# Sheet1.net
KiCad netlist of a schematic drawn in Altium Designer
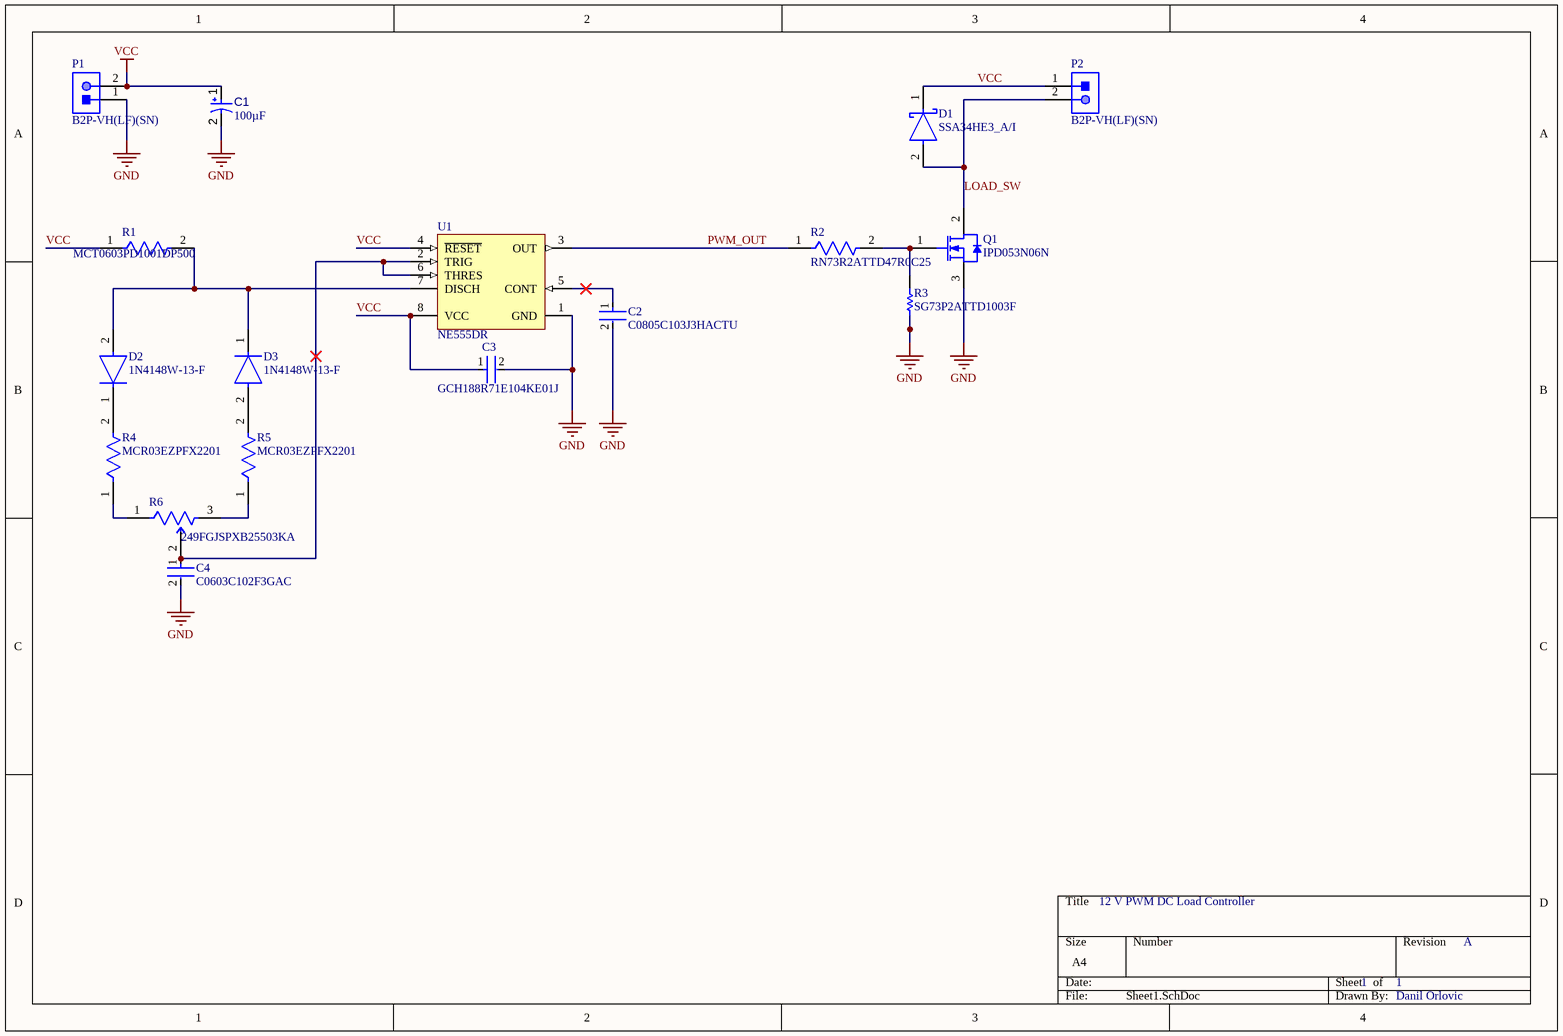
[diagram p0: Sheet1.SchDoc]

(export (version "E")
  (design (tool "Eeschema 10.0.6"))
  (components
    (comp (ref "C1")
      (value "100µF")
      (footprint "CAPPR65-350-1150X800X1250")
      (description "Aluminum Electrolytic Capacitor, 100 uF, +/- 20%, 50 V, -40 to 85 degC, 2-Pin THD, RoHS, Bulk")
      (fields (field (name "MANUFACTURER") "Panasonic") (field (name "TOLERANCE") "20%"))
      (libsource (lib "Danil Orlovic") (part "CAP-P-2"))
    )
    (comp (ref "C2")
      (value "C0805C103J3HACTU")
      (footprint "FP-C0805C-DN-MFG")
      (description "CAP CER 10000PF 25V X8R 0805")
      (fields (field (name "TOLERANCE") "0.05") (field (name "MANUFACTURER") "KEMET"))
      (libsource (lib "Altium Content Vault") (part "b4654b650e69147ec39a6b967a45e02"))
    )
    (comp (ref "C3")
      (value "GCH188R71E104KE01J")
      (footprint "FP-GCH188-0_1-e0_2_0_5-IPC_A")
      (description "Ceramic Capacitor 100nF ±10% 25V X7R 0603")
      (libsource (lib "Altium Content Vault") (part "b4654b650e69147ec39a6b967a45e02"))
    )
    (comp (ref "C4")
      (value "C0603C102F3GAC")
      (footprint "FP-C0603C-CF-MFG")
      (description "C0603 1,000 pF C0G 30ppm/°C 1.00% 25 V")
      (fields
        (field (name "OCTOPART") "https://octopart.com/c0603c102f3gac-kemet-9143535")
        (field (name "TOLERANCE") "0.01")
      )
      (libsource (lib "Altium Content Vault") (part "b4654b650e69147ec39a6b967a45e02"))
    )
    (comp (ref "D1")
      (value "SSA34HE3_A/I")
      (footprint "FP-95400-MFG")
      (description "DIODE SCHOTTKY 40V 3A DO214AC")
      (libsource (lib "Altium Content Vault") (part "1d6ec82d83fb6aee721767c19dac4b9"))
    )
    (comp (ref "D2")
      (value "1N4148W-13-F")
      (footprint "FP-SOD123-MFG")
      (description "DIODE GEN PURP 100V 150MA SOD123")
      (fields
        (field (name "OCTOPART") "https://octopart.com/1n4148w-13-f-diodes+inc.-2359612")
        (field (name "MANUFACTURER") "Diodes Inc.")
      )
      (libsource (lib "Altium Content Vault") (part "d7152d700b627762746794eb795d46e"))
    )
    (comp (ref "D3")
      (value "1N4148W-13-F")
      (footprint "FP-SOD123-MFG")
      (description "DIODE GEN PURP 100V 150MA SOD123")
      (fields
        (field (name "OCTOPART") "https://octopart.com/1n4148w-13-f-diodes+inc.-2359612")
        (field (name "MANUFACTURER") "Diodes Inc.")
      )
      (libsource (lib "Altium Content Vault") (part "d7152d700b627762746794eb795d46e"))
    )
    (comp (ref "P1")
      (value "B2P-VH(LF)(SN)")
      (footprint "JST-B2P-VH(LF)(SN)_V")
      (fields (field (name "MANUFACTURER") "JST"))
      (libsource (lib "Danil Orlovic") (part "CN-1P-M-R2"))
    )
    (comp (ref "P2")
      (value "B2P-VH(LF)(SN)")
      (footprint "JST-B2P-VH(LF)(SN)_V")
      (fields (field (name "MANUFACTURER") "JST"))
      (libsource (lib "") (part "CN-1P-M-R2_1"))
    )
    (comp (ref "Q1")
      (value "IPD053N06N")
      (footprint "INF-PG-TO252-3-11_A_M")
      (description "N-Channel OptiMOS Power-Transistor, 60 V VDS, 45 A ID, -55 to 175 degC, PG-TO252-3-11, Reel, Green")
      (fields (field (name "MANUFACTURER") "Infineon"))
      (libsource (lib "Altium Content Vault") (part "INF-NEMOS-GDS-3"))
    )
    (comp (ref "R1")
      (value "MCT0603PD1001DP500")
      (footprint "FP-MCT0603-IPC_C")
      (description "RES SMD 100 OHM 1% 1/8W 0603")
      (fields (field (name "TOLERANCE") "0.5%"))
      (libsource (lib "Altium Content Vault") (part "1029c3af85768c4190bb7ad29bc67b5"))
    )
    (comp (ref "R2")
      (value "RN73R2ATTD47R0C25")
      (footprint "FP-RN73R2A-IPC_B")
      (description "47Ω ±0.25% 0.125W, 1/8W Chip Resistor 0805 (2012 Metric) Moisture Resistant Thin Film")
      (libsource (lib "Altium Content Vault") (part "1029c3af85768c4190bb7ad29bc67b5"))
    )
    (comp (ref "R3")
      (value "SG73P2ATTD1003F")
      (footprint "RESC2013X60X30NL20T20")
      (fields (field (name "MANUFACTURER") "KOA Speer"))
      (libsource (lib "Altium Content Vault") (part "RES"))
    )
    (comp (ref "R4")
      (value "MCR03EZPFX2201")
      (footprint "FP-MCR03-IPC_C")
      (description "Thick Film Chip Resistor, 0603, 2.2kΩ, 1%, 100ppm/°C, 0.1W, 50V")
      (fields (field (name "TOLERANCE") "1%"))
      (libsource (lib "Altium Content Vault") (part "1029c3af85768c4190bb7ad29bc67b5"))
    )
    (comp (ref "R5")
      (value "MCR03EZPFX2201")
      (footprint "FP-MCR03-IPC_C")
      (description "Thick Film Chip Resistor, 0603, 2.2kΩ, 1%, 100ppm/°C, 0.1W, 50V")
      (fields (field (name "TOLERANCE") "1%"))
      (libsource (lib "Altium Content Vault") (part "1029c3af85768c4190bb7ad29bc67b5"))
    )
    (comp (ref "R6")
      (value "249FGJSPXB25503KA")
      (footprint "FP-249FGJSPXB25503KA-MFG")
      (fields (field (name "TOLERANCE") "10%"))
      (libsource (lib "Altium Content Vault") (part "a77ee20e32664c43a3a1dd5392b6021"))
    )
    (comp (ref "U1")
      (value "NE555DR")
      (footprint "D0008A_N")
      (description "Precision Timer, 4.5 to 16 V, 0 to 70 degC, 8-Pin SOIC (D), Green (RoHS & no Sb/Br), Tape and Reel")
      (fields (field (name "MANUFACTURER") "Texas Instruments"))
      (libsource (lib "Danil Orlovic") (part "TI-NE555-P-8"))
    )
  )
  (nets
    (net (code "2") (name "/LOAD_SW") (class "Default")
      (node (ref "D1") (pin "2") (pinfunction "A_2") (pintype "passive"))
      (node (ref "P2") (pin "2") (pinfunction "2_2") (pintype "passive"))
      (node (ref "Q1") (pin "2") (pinfunction "DRAIN_2") (pintype "passive"))
    )
    (net (code "3") (name "/PWM_OUT") (class "Default")
      (node (ref "R2") (pin "1") (pinfunction "1_1") (pintype "passive"))
      (node (ref "U1") (pin "3") (pinfunction "OUT_3") (pintype "output"))
    )
    (net (code "4") (name "GND") (class "Default")
      (node (ref "C1") (pin "2") (pinfunction "2_2") (pintype "passive"))
      (node (ref "C2") (pin "2") (pinfunction "2_2") (pintype "passive"))
      (node (ref "C3") (pin "2") (pinfunction "2_2") (pintype "passive"))
      (node (ref "C4") (pin "2") (pinfunction "2_2") (pintype "passive"))
      (node (ref "P1") (pin "1") (pinfunction "1_1") (pintype "passive"))
      (node (ref "Q1") (pin "3") (pinfunction "SOURCE_3") (pintype "passive"))
      (node (ref "R3") (pin "1") (pinfunction "1_1") (pintype "passive"))
      (node (ref "U1") (pin "1") (pinfunction "GND_1") (pintype "power_in"))
    )
    (net (code "5") (name "Net-(D2-A)") (class "Default")
      (node (ref "D2") (pin "2") (pinfunction "A_2") (pintype "passive"))
      (node (ref "D3") (pin "1") (pinfunction "C_1") (pintype "passive"))
      (node (ref "R1") (pin "2") (pinfunction "2_2") (pintype "passive"))
      (node (ref "U1") (pin "7") (pinfunction "DISCH_7") (pintype "open_collector"))
    )
    (net (code "6") (name "Net-(D2-C)") (class "Default")
      (node (ref "D2") (pin "1") (pinfunction "C_1") (pintype "passive"))
      (node (ref "R4") (pin "2") (pinfunction "2_2") (pintype "passive"))
    )
    (net (code "7") (name "Net-(D3-A)") (class "Default")
      (node (ref "D3") (pin "2") (pinfunction "A_2") (pintype "passive"))
      (node (ref "R5") (pin "2") (pinfunction "2_2") (pintype "passive"))
    )
    (net (code "8") (name "Net-(Q1-GATE)") (class "Default")
      (node (ref "Q1") (pin "1") (pinfunction "GATE_1") (pintype "passive"))
      (node (ref "R2") (pin "2") (pinfunction "2_2") (pintype "passive"))
      (node (ref "R3") (pin "2") (pinfunction "2_2") (pintype "passive"))
    )
    (net (code "9") (name "Net-(R4-Pad1)") (class "Default")
      (node (ref "R4") (pin "1") (pinfunction "1_1") (pintype "passive"))
      (node (ref "R6") (pin "1") (pinfunction "1_1") (pintype "passive"))
    )
    (net (code "10") (name "Net-(R5-Pad1)") (class "Default")
      (node (ref "R5") (pin "1") (pinfunction "1_1") (pintype "passive"))
      (node (ref "R6") (pin "3") (pinfunction "3_3") (pintype "passive"))
    )
    (net (code "11") (name "Net-(U1-CONT)") (class "Default")
      (node (ref "C2") (pin "1") (pinfunction "1_1") (pintype "passive"))
      (node (ref "U1") (pin "5") (pinfunction "CONT_5") (pintype "input"))
    )
    (net (code "12") (name "Net-(U1-THRES)") (class "Default")
      (node (ref "C4") (pin "1") (pinfunction "1_1") (pintype "passive"))
      (node (ref "R6") (pin "2") (pinfunction "2_2") (pintype "passive"))
      (node (ref "U1") (pin "2") (pinfunction "TRIG_2") (pintype "input"))
      (node (ref "U1") (pin "6") (pinfunction "THRES_6") (pintype "input"))
    )
    (net (code "13") (name "VCC") (class "Default")
      (node (ref "C1") (pin "1") (pinfunction "1_1") (pintype "passive"))
      (node (ref "C3") (pin "1") (pinfunction "1_1") (pintype "passive"))
      (node (ref "D1") (pin "1") (pinfunction "C_1") (pintype "passive"))
      (node (ref "P1") (pin "2") (pinfunction "2_2") (pintype "passive"))
      (node (ref "P2") (pin "1") (pinfunction "1_1") (pintype "passive"))
      (node (ref "R1") (pin "1") (pinfunction "1_1") (pintype "passive"))
      (node (ref "U1") (pin "4") (pinfunction "~{RESET}_4") (pintype "input"))
      (node (ref "U1") (pin "8") (pinfunction "VCC_8") (pintype "power_in"))
    )
  )
)
